# Qwiic_Iridium_9603N.net
KiCad netlist of a schematic drawn in EAGLE
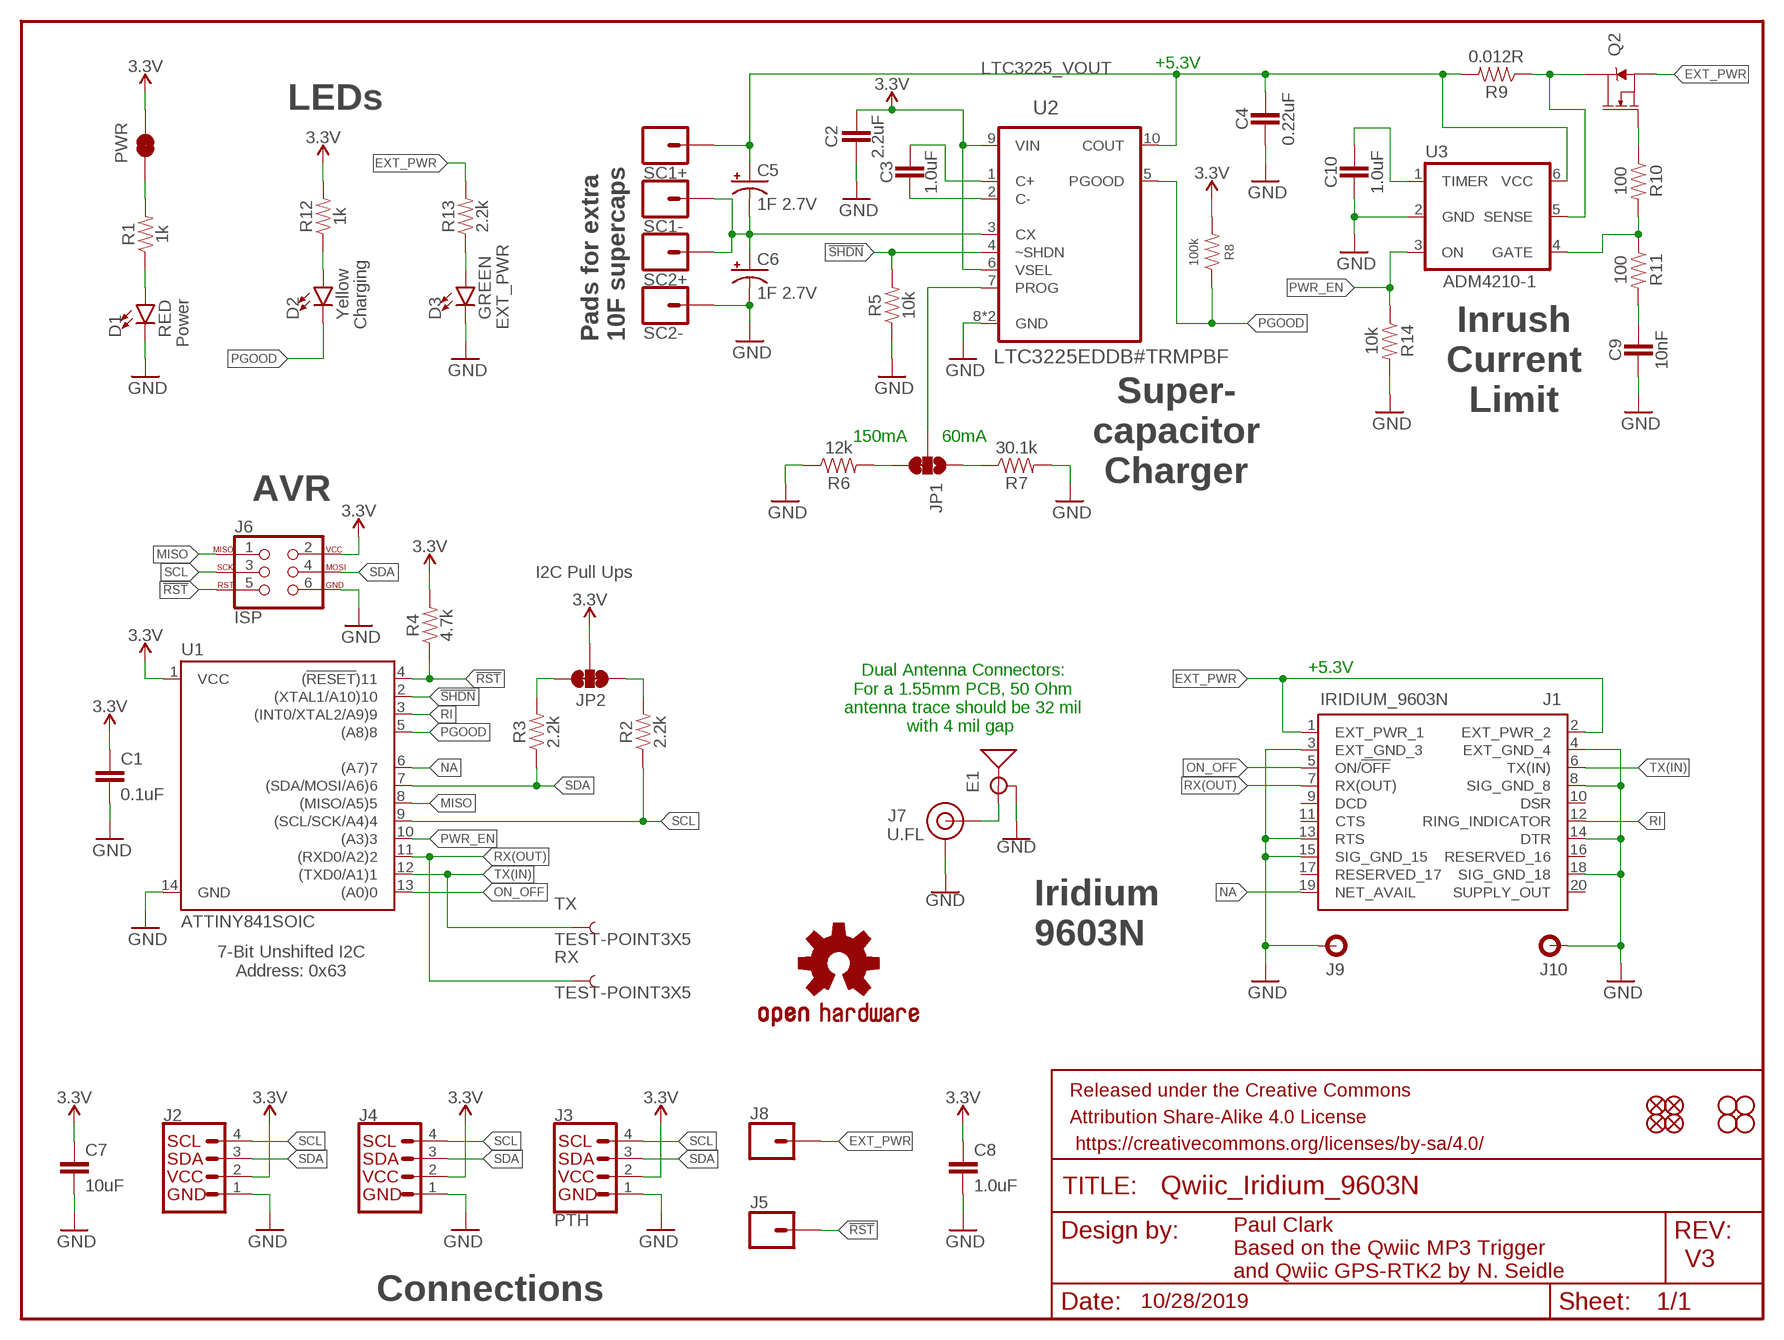
[diagram p0: schematic, sheet 1]

(export (version "E")
  (design (tool "Eeschema 10.0.6"))
  (components
    (comp (ref "C1")
      (value "0.1uF")
      (footprint "eagle-import:0603")
      (libsource (lib "eagle-import") (part "0.1UF-0603-25V-5%"))
    )
    (comp (ref "C2")
      (value "2.2uF")
      (footprint "eagle-import:0603")
      (libsource (lib "eagle-import") (part "2.2UF-0603-10V-20%"))
    )
    (comp (ref "C3")
      (value "1.0uF")
      (footprint "eagle-import:0603")
      (libsource (lib "eagle-import") (part "1.0UF-0603-16V-10%-X7R"))
    )
    (comp (ref "C4")
      (value "0.22uF")
      (footprint "eagle-import:0603")
      (libsource (lib "eagle-import") (part "0.22UF-0603-25V-10%"))
    )
    (comp (ref "C5")
      (value "1F 2.7V")
      (footprint "eagle-import:CPOL-RADIAL-1F-2.7V")
      (libsource (lib "eagle-import") (part "1F-2.7V(PTH)CPOL-RADIAL-1H-2.7V"))
    )
    (comp (ref "C6")
      (value "1F 2.7V")
      (footprint "eagle-import:CPOL-RADIAL-1F-2.7V")
      (libsource (lib "eagle-import") (part "1F-2.7V(PTH)CPOL-RADIAL-1H-2.7V"))
    )
    (comp (ref "C7")
      (value "10uF")
      (footprint "eagle-import:0603")
      (libsource (lib "eagle-import") (part "10UF-0603-6.3V-20%"))
    )
    (comp (ref "C8")
      (value "1.0uF")
      (footprint "eagle-import:0603")
      (libsource (lib "eagle-import") (part "1.0UF-0603-16V-10%-X7R"))
    )
    (comp (ref "C9")
      (value "10nF")
      (footprint "eagle-import:0603")
      (libsource (lib "eagle-import") (part "10NF-0603-50V-10%"))
    )
    (comp (ref "C10")
      (value "1.0uF")
      (footprint "eagle-import:0603")
      (libsource (lib "eagle-import") (part "1.0UF-0603-16V-10%-X7R"))
    )
    (comp (ref "D1")
      (value "RED")
      (footprint "eagle-import:LED-0603")
      (libsource (lib "eagle-import") (part "LED-RED0603"))
    )
    (comp (ref "D2")
      (value "Yellow")
      (footprint "eagle-import:LED-0603")
      (libsource (lib "eagle-import") (part "LED-YELLOW0603"))
    )
    (comp (ref "D3")
      (value "GREEN")
      (footprint "eagle-import:LED-0603")
      (libsource (lib "eagle-import") (part "LED-GREEN0603"))
    )
    (comp (ref "E1")
      (value "ANTENNA-GROUNDEDEDGE_SMA")
      (footprint "eagle-import:SMA-EDGE")
      (libsource (lib "eagle-import") (part "ANTENNA-GROUNDEDEDGE_SMA"))
    )
    (comp (ref "FRAME1")
      (value "FRAME-LETTER")
      (footprint "eagle-import:CREATIVE_COMMONS")
      (libsource (lib "eagle-import") (part "FRAME-LETTER"))
    )
    (comp (ref "J1")
      (value "IRIDIUM_9603N")
      (footprint "eagle-import:IRIDIUM_9603N")
      (libsource (lib "eagle-import") (part "IRIDIUM_9603N"))
    )
    (comp (ref "J2")
      (value "QWIIC_CONNECTORJS-1MM")
      (footprint "eagle-import:JST04_1MM_RA")
      (libsource (lib "eagle-import") (part "QWIIC_CONNECTORJS-1MM"))
    )
    (comp (ref "J3")
      (value "PTH")
      (footprint "eagle-import:1X04_NO_SILK")
      (libsource (lib "eagle-import") (part "I2C_STANDARD_NO_SILK"))
    )
    (comp (ref "J4")
      (value "QWIIC_CONNECTORJS-1MM")
      (footprint "eagle-import:JST04_1MM_RA")
      (libsource (lib "eagle-import") (part "QWIIC_CONNECTORJS-1MM"))
    )
    (comp (ref "J5")
      (value "CONN_01PTH_NO_SILK_YES_STOP")
      (footprint "eagle-import:1X01_NO_SILK")
      (libsource (lib "eagle-import") (part "CONN_01PTH_NO_SILK_YES_STOP"))
    )
    (comp (ref "J6")
      (value "ISP")
      (footprint "eagle-import:2X3_TEST_POINTS")
      (libsource (lib "eagle-import") (part "AVR_SPI_PROG_3X2TESTPOINTS"))
    )
    (comp (ref "J7")
      (value "U.FL")
      (footprint "eagle-import:U.FL")
      (libsource (lib "eagle-import") (part "U.FL2PIN"))
    )
    (comp (ref "J8")
      (value "CONN_01PTH_NO_SILK_YES_STOP")
      (footprint "eagle-import:1X01_NO_SILK")
      (libsource (lib "eagle-import") (part "CONN_01PTH_NO_SILK_YES_STOP"))
    )
    (comp (ref "J9")
      (value "STANDOFFS_M2X0.4_STEEL_6MM")
      (footprint "eagle-import:STANDOFF_M2X0.4")
      (libsource (lib "eagle-import") (part "STANDOFFS_M2X0.4_STEEL_6MM"))
    )
    (comp (ref "J10")
      (value "STANDOFFS_M2X0.4_STEEL_6MM")
      (footprint "eagle-import:STANDOFF_M2X0.4")
      (libsource (lib "eagle-import") (part "STANDOFFS_M2X0.4_STEEL_6MM"))
    )
    (comp (ref "JP1")
      (value "JUMPER-SMT_3_1-NC_TRACE_SILK")
      (footprint "eagle-import:SMT-JUMPER_3_1-NC_TRACE_SILK")
      (libsource (lib "eagle-import") (part "JUMPER-SMT_3_1-NC_TRACE_SILK"))
    )
    (comp (ref "JP2")
      (value "JUMPER-SMT_3_2-NC_TRACE_SILK")
      (footprint "eagle-import:SMT-JUMPER_3_2-NC_TRACE_SILK")
      (libsource (lib "eagle-import") (part "JUMPER-SMT_3_2-NC_TRACE_SILK"))
    )
    (comp (ref "JP3")
      (value "STAND-OFF")
      (footprint "eagle-import:STAND-OFF")
      (libsource (lib "eagle-import") (part "STAND-OFF"))
    )
    (comp (ref "JP4")
      (value "STAND-OFF")
      (footprint "eagle-import:STAND-OFF")
      (libsource (lib "eagle-import") (part "STAND-OFF"))
    )
    (comp (ref "JP5")
      (value "FIDUCIAL1X2")
      (footprint "eagle-import:FIDUCIAL-1X2")
      (libsource (lib "eagle-import") (part "FIDUCIAL1X2"))
    )
    (comp (ref "JP6")
      (value "FIDUCIAL1X2")
      (footprint "eagle-import:FIDUCIAL-1X2")
      (libsource (lib "eagle-import") (part "FIDUCIAL1X2"))
    )
    (comp (ref "JP7")
      (value "FIDUCIAL1X2")
      (footprint "eagle-import:FIDUCIAL-1X2")
      (libsource (lib "eagle-import") (part "FIDUCIAL1X2"))
    )
    (comp (ref "JP8")
      (value "FIDUCIAL1X2")
      (footprint "eagle-import:FIDUCIAL-1X2")
      (libsource (lib "eagle-import") (part "FIDUCIAL1X2"))
    )
    (comp (ref "JP9")
      (value "STAND-OFF")
      (footprint "eagle-import:STAND-OFF")
      (libsource (lib "eagle-import") (part "STAND-OFF"))
    )
    (comp (ref "JP10")
      (value "STAND-OFF")
      (footprint "eagle-import:STAND-OFF")
      (libsource (lib "eagle-import") (part "STAND-OFF"))
    )
    (comp (ref "LOGO1")
      (value "OSHW-LOGOMINI")
      (footprint "eagle-import:OSHW-LOGO-MINI")
      (libsource (lib "eagle-import") (part "OSHW-LOGOMINI"))
    )
    (comp (ref "PWR")
      (value "JUMPER-SMT_2_NC_TRACE_SILK")
      (footprint "eagle-import:SMT-JUMPER_2_NC_TRACE_SILK")
      (libsource (lib "eagle-import") (part "JUMPER-SMT_2_NC_TRACE_SILK"))
    )
    (comp (ref "Q2")
      (value "5.8A/30V/35mΩ")
      (footprint "eagle-import:SOT23-3")
      (libsource (lib "eagle-import") (part "MOSFET-NCH-AO3404A"))
    )
    (comp (ref "R1")
      (value "1k")
      (footprint "eagle-import:0603")
      (libsource (lib "eagle-import") (part "1KOHM-0603-1/10W-1%"))
    )
    (comp (ref "R2")
      (value "2.2k")
      (footprint "eagle-import:0603")
      (libsource (lib "eagle-import") (part "2.2KOHM-0603-1/10W-1%"))
    )
    (comp (ref "R3")
      (value "2.2k")
      (footprint "eagle-import:0603")
      (libsource (lib "eagle-import") (part "2.2KOHM-0603-1/10W-1%"))
    )
    (comp (ref "R4")
      (value "4.7k")
      (footprint "eagle-import:0603")
      (libsource (lib "eagle-import") (part "4.7KOHM-0603-1/10W-1%"))
    )
    (comp (ref "R5")
      (value "10k")
      (footprint "eagle-import:0603")
      (libsource (lib "eagle-import") (part "10KOHM-0603-1/10W-1%"))
    )
    (comp (ref "R6")
      (value "12k")
      (footprint "eagle-import:0603")
      (libsource (lib "eagle-import") (part "12KOHM-0603-1/10W-1%"))
    )
    (comp (ref "R7")
      (value "30.1k")
      (footprint "eagle-import:0603")
      (libsource (lib "eagle-import") (part "30.1KOHM-0603-1/10W-1%"))
    )
    (comp (ref "R8")
      (value "100k")
      (footprint "eagle-import:0603")
      (libsource (lib "eagle-import") (part "100KOHM-0603-1/10W-1%"))
    )
    (comp (ref "R9")
      (value "0.012R")
      (footprint "eagle-import:0603")
      (libsource (lib "eagle-import") (part "RESISTOR_0603_12MILLIOHM0603"))
    )
    (comp (ref "R10")
      (value "100")
      (footprint "eagle-import:0603")
      (libsource (lib "eagle-import") (part "100OHM-0603-1/10W-1%"))
    )
    (comp (ref "R11")
      (value "100")
      (footprint "eagle-import:0603")
      (libsource (lib "eagle-import") (part "100OHM-0603-1/10W-1%"))
    )
    (comp (ref "R12")
      (value "1k")
      (footprint "eagle-import:0603")
      (libsource (lib "eagle-import") (part "1KOHM-0603-1/10W-1%"))
    )
    (comp (ref "R13")
      (value "2.2k")
      (footprint "eagle-import:0603")
      (libsource (lib "eagle-import") (part "2.2KOHM-0603-1/10W-1%"))
    )
    (comp (ref "R14")
      (value "10k")
      (footprint "eagle-import:0603")
      (libsource (lib "eagle-import") (part "10KOHM-0603-1/10W-1%"))
    )
    (comp (ref "RX")
      (value "TEST-POINT3X5")
      (footprint "eagle-import:PAD.03X.05")
      (libsource (lib "eagle-import") (part "TEST-POINT3X5"))
    )
    (comp (ref "SC1+")
      (value "CONN_01PTH_NO_SILK_YES_STOP")
      (footprint "eagle-import:1X01_NO_SILK")
      (libsource (lib "eagle-import") (part "CONN_01PTH_NO_SILK_YES_STOP"))
    )
    (comp (ref "SC1-")
      (value "CONN_01PTH_NO_SILK_YES_STOP")
      (footprint "eagle-import:1X01_NO_SILK")
      (libsource (lib "eagle-import") (part "CONN_01PTH_NO_SILK_YES_STOP"))
    )
    (comp (ref "SC2+")
      (value "CONN_01PTH_NO_SILK_YES_STOP")
      (footprint "eagle-import:1X01_NO_SILK")
      (libsource (lib "eagle-import") (part "CONN_01PTH_NO_SILK_YES_STOP"))
    )
    (comp (ref "SC2-")
      (value "CONN_01PTH_NO_SILK_YES_STOP")
      (footprint "eagle-import:1X01_NO_SILK")
      (libsource (lib "eagle-import") (part "CONN_01PTH_NO_SILK_YES_STOP"))
    )
    (comp (ref "TX")
      (value "TEST-POINT3X5")
      (footprint "eagle-import:PAD.03X.05")
      (libsource (lib "eagle-import") (part "TEST-POINT3X5"))
    )
    (comp (ref "U1")
      (value "ATTINY841SOIC")
      (footprint "eagle-import:ATTINY841")
      (libsource (lib "eagle-import") (part "ATTINY841SOIC"))
    )
    (comp (ref "U2")
      (value "LTC3225EDDB#TRMPBF")
      (footprint "eagle-import:DFN300X200-10L")
      (libsource (lib "eagle-import") (part "LTC3225EDDB-TRMPBFDFN300X200-10L"))
    )
    (comp (ref "U3")
      (value "ADM4210-1")
      (footprint "eagle-import:TSOT6")
      (libsource (lib "eagle-import") (part "ADM4210-1"))
    )
  )
  (nets
    (net (code "1") (name "/LTC3225_VOUT") (class "Default")
      (node (ref "C4") (pin "1") (pinfunction "1_1") (pintype "passive"))
      (node (ref "C5") (pin "+") (pinfunction "+_+") (pintype "passive"))
      (node (ref "R9") (pin "2") (pinfunction "2_2") (pintype "passive"))
      (node (ref "SC1+") (pin "1") (pinfunction "1_1") (pintype "passive"))
      (node (ref "U2") (pin "10") (pinfunction "COUT_10") (pintype "output"))
      (node (ref "U3") (pin "6") (pinfunction "VCC_6") (pintype "power_in"))
    )
    (net (code "2") (name "/~{RST}") (class "Default")
      (node (ref "J5") (pin "1") (pinfunction "1_1") (pintype "passive"))
      (node (ref "J6") (pin "5") (pinfunction "5_5") (pintype "passive"))
      (node (ref "R4") (pin "1") (pinfunction "1_1") (pintype "passive"))
      (node (ref "U1") (pin "4") (pinfunction "(~{RESET})11_4") (pintype "bidirectional"))
    )
    (net (code "3") (name "/~{SHDN}") (class "Default")
      (node (ref "R5") (pin "2") (pinfunction "2_2") (pintype "passive"))
      (node (ref "U1") (pin "2") (pinfunction "(XTAL1/A10)10_2") (pintype "bidirectional"))
      (node (ref "U2") (pin "4") (pinfunction "~{SHDN}_4") (pintype "input"))
    )
    (net (code "4") (name "3.3V") (class "Default")
      (node (ref "C1") (pin "1") (pinfunction "1_1") (pintype "passive"))
      (node (ref "C2") (pin "1") (pinfunction "1_1") (pintype "passive"))
      (node (ref "C7") (pin "1") (pinfunction "1_1") (pintype "passive"))
      (node (ref "C8") (pin "1") (pinfunction "1_1") (pintype "passive"))
      (node (ref "J2") (pin "2") (pinfunction "2_2") (pintype "power_in"))
      (node (ref "J3") (pin "2") (pinfunction "VCC_2") (pintype "power_in"))
      (node (ref "J4") (pin "2") (pinfunction "2_2") (pintype "power_in"))
      (node (ref "J6") (pin "2") (pinfunction "2_2") (pintype "passive"))
      (node (ref "JP2") (pin "2") (pinfunction "2_2") (pintype "passive"))
      (node (ref "PWR") (pin "2") (pinfunction "2_2") (pintype "passive"))
      (node (ref "R12") (pin "2") (pinfunction "2_2") (pintype "passive"))
      (node (ref "R4") (pin "2") (pinfunction "2_2") (pintype "passive"))
      (node (ref "R8") (pin "2") (pinfunction "2_2") (pintype "passive"))
      (node (ref "U1") (pin "1") (pinfunction "VCC_1") (pintype "bidirectional"))
      (node (ref "U2") (pin "6") (pinfunction "VSEL_6") (pintype "input"))
      (node (ref "U2") (pin "9") (pinfunction "VIN_9") (pintype "power_in"))
    )
    (net (code "5") (name "EXT_PWR") (class "Default")
      (node (ref "J1") (pin "1") (pinfunction "EXT_PWR_1_1") (pintype "power_in"))
      (node (ref "J1") (pin "2") (pinfunction "EXT_PWR_2_2") (pintype "power_in"))
      (node (ref "J8") (pin "1") (pinfunction "1_1") (pintype "passive"))
      (node (ref "Q2") (pin "2") (pinfunction "S_2") (pintype "bidirectional"))
      (node (ref "R13") (pin "2") (pinfunction "2_2") (pintype "passive"))
    )
    (net (code "6") (name "GND") (class "Default")
      (node (ref "C1") (pin "2") (pinfunction "2_2") (pintype "passive"))
      (node (ref "C10") (pin "2") (pinfunction "2_2") (pintype "passive"))
      (node (ref "C2") (pin "2") (pinfunction "2_2") (pintype "passive"))
      (node (ref "C4") (pin "2") (pinfunction "2_2") (pintype "passive"))
      (node (ref "C6") (pin "-") (pinfunction "-_-") (pintype "passive"))
      (node (ref "C7") (pin "2") (pinfunction "2_2") (pintype "passive"))
      (node (ref "C8") (pin "2") (pinfunction "2_2") (pintype "passive"))
      (node (ref "C9") (pin "2") (pinfunction "2_2") (pintype "passive"))
      (node (ref "D1") (pin "C") (pinfunction "C_C") (pintype "passive"))
      (node (ref "D3") (pin "C") (pinfunction "C_C") (pintype "passive"))
      (node (ref "E1") (pin "GND@0") (pinfunction "GND_GND@0") (pintype "bidirectional"))
      (node (ref "E1") (pin "GND@1") (pinfunction "GND_GND@1") (pintype "bidirectional"))
      (node (ref "E1") (pin "GND@2") (pinfunction "GND_GND@2") (pintype "bidirectional"))
      (node (ref "E1") (pin "GND@3") (pinfunction "GND_GND@3") (pintype "bidirectional"))
      (node (ref "J1") (pin "13") (pinfunction "RTS_13") (pintype "input"))
      (node (ref "J1") (pin "14") (pinfunction "DTR_14") (pintype "input"))
      (node (ref "J1") (pin "15") (pinfunction "SIG_GND_15_15") (pintype "power_in"))
      (node (ref "J1") (pin "18") (pinfunction "SIG_GND_18_18") (pintype "power_in"))
      (node (ref "J1") (pin "3") (pinfunction "EXT_GND_3_3") (pintype "power_in"))
      (node (ref "J1") (pin "4") (pinfunction "EXT_GND_4_4") (pintype "power_in"))
      (node (ref "J1") (pin "8") (pinfunction "SIG_GND_8_8") (pintype "power_in"))
      (node (ref "J10") (pin "1") (pinfunction "1_1") (pintype "bidirectional"))
      (node (ref "J2") (pin "1") (pinfunction "1_1") (pintype "power_in"))
      (node (ref "J3") (pin "1") (pinfunction "GND_1") (pintype "power_in"))
      (node (ref "J4") (pin "1") (pinfunction "1_1") (pintype "power_in"))
      (node (ref "J6") (pin "6") (pinfunction "6_6") (pintype "passive"))
      (node (ref "J7") (pin "1") (pinfunction "GND_1") (pintype "bidirectional"))
      (node (ref "J7") (pin "2") (pinfunction "GND_2") (pintype "bidirectional"))
      (node (ref "J9") (pin "1") (pinfunction "1_1") (pintype "bidirectional"))
      (node (ref "R14") (pin "2") (pinfunction "2_2") (pintype "passive"))
      (node (ref "R5") (pin "1") (pinfunction "1_1") (pintype "passive"))
      (node (ref "R6") (pin "1") (pinfunction "1_1") (pintype "passive"))
      (node (ref "R7") (pin "2") (pinfunction "2_2") (pintype "passive"))
      (node (ref "SC2-") (pin "1") (pinfunction "1_1") (pintype "passive"))
      (node (ref "U1") (pin "14") (pinfunction "GND_14") (pintype "bidirectional"))
      (node (ref "U2") (pin "11") (pinfunction "GND_11") (pintype "passive"))
      (node (ref "U2") (pin "8") (pinfunction "GND_8") (pintype "passive"))
      (node (ref "U3") (pin "2") (pinfunction "GND_2") (pintype "power_in"))
    )
    (net (code "7") (name "MISO") (class "Default")
      (node (ref "J6") (pin "1") (pinfunction "1_1") (pintype "passive"))
      (node (ref "U1") (pin "8") (pinfunction "(MISO/A5)5_8") (pintype "bidirectional"))
    )
    (net (code "8") (name "NA") (class "Default")
      (node (ref "J1") (pin "19") (pinfunction "NET_AVAIL_19") (pintype "output"))
      (node (ref "U1") (pin "6") (pinfunction "(A7)7_6") (pintype "bidirectional"))
    )
    (net (code "9") (name "Net-(C9-Pad1)") (class "Default")
      (node (ref "C9") (pin "1") (pinfunction "1_1") (pintype "passive"))
      (node (ref "R11") (pin "2") (pinfunction "2_2") (pintype "passive"))
    )
    (net (code "10") (name "Net-(D1-PadA)") (class "Default")
      (node (ref "D1") (pin "A") (pinfunction "A_A") (pintype "passive"))
      (node (ref "R1") (pin "1") (pinfunction "1_1") (pintype "passive"))
    )
    (net (code "11") (name "Net-(D2-PadA)") (class "Default")
      (node (ref "D2") (pin "A") (pinfunction "A_A") (pintype "passive"))
      (node (ref "R12") (pin "1") (pinfunction "1_1") (pintype "passive"))
    )
    (net (code "12") (name "Net-(D3-PadA)") (class "Default")
      (node (ref "D3") (pin "A") (pinfunction "A_A") (pintype "passive"))
      (node (ref "R13") (pin "1") (pinfunction "1_1") (pintype "passive"))
    )
    (net (code "13") (name "Net-(E1-SIGNAL)") (class "Default")
      (node (ref "E1") (pin "SIG") (pinfunction "SIGNAL_SIG") (pintype "bidirectional"))
      (node (ref "J7") (pin "FEED") (pinfunction "SIGNAL_FEED") (pintype "bidirectional"))
    )
    (net (code "14") (name "Net-(JP1-Pad1)") (class "Default")
      (node (ref "JP1") (pin "1") (pinfunction "1_1") (pintype "passive"))
      (node (ref "R7") (pin "1") (pinfunction "1_1") (pintype "passive"))
    )
    (net (code "15") (name "Net-(JP1-Pad3)") (class "Default")
      (node (ref "JP1") (pin "3") (pinfunction "3_3") (pintype "passive"))
      (node (ref "R6") (pin "2") (pinfunction "2_2") (pintype "passive"))
    )
    (net (code "16") (name "Net-(JP2-Pad1)") (class "Default")
      (node (ref "JP2") (pin "1") (pinfunction "1_1") (pintype "passive"))
      (node (ref "R2") (pin "2") (pinfunction "2_2") (pintype "passive"))
    )
    (net (code "17") (name "Net-(JP2-Pad3)") (class "Default")
      (node (ref "JP2") (pin "3") (pinfunction "3_3") (pintype "passive"))
      (node (ref "R3") (pin "2") (pinfunction "2_2") (pintype "passive"))
    )
    (net (code "18") (name "Net-(PWR-Pad1)") (class "Default")
      (node (ref "PWR") (pin "1") (pinfunction "1_1") (pintype "passive"))
      (node (ref "R1") (pin "2") (pinfunction "2_2") (pintype "passive"))
    )
    (net (code "19") (name "Net-(Q2-D)") (class "Default")
      (node (ref "Q2") (pin "3") (pinfunction "D_3") (pintype "bidirectional"))
      (node (ref "R9") (pin "1") (pinfunction "1_1") (pintype "passive"))
      (node (ref "U3") (pin "5") (pinfunction "SENSE_5") (pintype "input"))
    )
    (net (code "20") (name "Net-(Q2-G)") (class "Default")
      (node (ref "Q2") (pin "1") (pinfunction "G_1") (pintype "bidirectional"))
      (node (ref "R10") (pin "1") (pinfunction "1_1") (pintype "passive"))
    )
    (net (code "21") (name "Net-(U2-C+)") (class "Default")
      (node (ref "C3") (pin "1") (pinfunction "1_1") (pintype "passive"))
      (node (ref "U2") (pin "1") (pinfunction "C+_1") (pintype "passive"))
    )
    (net (code "22") (name "Net-(U2-C-)") (class "Default")
      (node (ref "C3") (pin "2") (pinfunction "2_2") (pintype "passive"))
      (node (ref "U2") (pin "2") (pinfunction "C-_2") (pintype "passive"))
    )
    (net (code "23") (name "Net-(U2-CX)") (class "Default")
      (node (ref "C5") (pin "-") (pinfunction "-_-") (pintype "passive"))
      (node (ref "C6") (pin "+") (pinfunction "+_+") (pintype "passive"))
      (node (ref "SC1-") (pin "1") (pinfunction "1_1") (pintype "passive"))
      (node (ref "SC2+") (pin "1") (pinfunction "1_1") (pintype "passive"))
      (node (ref "U2") (pin "3") (pinfunction "CX_3") (pintype "passive"))
    )
    (net (code "24") (name "Net-(U2-PROG)") (class "Default")
      (node (ref "JP1") (pin "2") (pinfunction "2_2") (pintype "passive"))
      (node (ref "U2") (pin "7") (pinfunction "PROG_7") (pintype "input"))
    )
    (net (code "25") (name "Net-(U3-GATE)") (class "Default")
      (node (ref "R10") (pin "2") (pinfunction "2_2") (pintype "passive"))
      (node (ref "R11") (pin "1") (pinfunction "1_1") (pintype "passive"))
      (node (ref "U3") (pin "4") (pinfunction "GATE_4") (pintype "output"))
    )
    (net (code "26") (name "Net-(U3-TIMER)") (class "Default")
      (node (ref "C10") (pin "1") (pinfunction "1_1") (pintype "passive"))
      (node (ref "U3") (pin "1") (pinfunction "TIMER_1") (pintype "input"))
    )
    (net (code "27") (name "ON_OFF") (class "Default")
      (node (ref "J1") (pin "5") (pinfunction "ON/~{OFF}_5") (pintype "input"))
      (node (ref "U1") (pin "13") (pinfunction "(A0)0_13") (pintype "bidirectional"))
    )
    (net (code "28") (name "PGOOD") (class "Default")
      (node (ref "D2") (pin "C") (pinfunction "C_C") (pintype "passive"))
      (node (ref "R8") (pin "1") (pinfunction "1_1") (pintype "passive"))
      (node (ref "U1") (pin "5") (pinfunction "(A8)8_5") (pintype "bidirectional"))
      (node (ref "U2") (pin "5") (pinfunction "PGOOD_5") (pintype "output"))
    )
    (net (code "29") (name "PWR_EN") (class "Default")
      (node (ref "R14") (pin "1") (pinfunction "1_1") (pintype "passive"))
      (node (ref "U1") (pin "10") (pinfunction "(A3)3_10") (pintype "bidirectional"))
      (node (ref "U3") (pin "3") (pinfunction "ON_3") (pintype "input"))
    )
    (net (code "30") (name "RI") (class "Default")
      (node (ref "J1") (pin "12") (pinfunction "RING_INDICATOR_12") (pintype "output"))
      (node (ref "U1") (pin "3") (pinfunction "(INT0/XTAL2/A9)9_3") (pintype "bidirectional"))
    )
    (net (code "31") (name "RX(OUT)") (class "Default")
      (node (ref "J1") (pin "7") (pinfunction "RX(OUT)_7") (pintype "output"))
      (node (ref "RX") (pin "P$1") (pinfunction "1_P$1") (pintype "bidirectional"))
      (node (ref "U1") (pin "11") (pinfunction "(RXD0/A2)2_11") (pintype "bidirectional"))
    )
    (net (code "32") (name "SCL") (class "Default")
      (node (ref "J2") (pin "4") (pinfunction "4_4") (pintype "passive"))
      (node (ref "J3") (pin "4") (pinfunction "SCL_4") (pintype "passive"))
      (node (ref "J4") (pin "4") (pinfunction "4_4") (pintype "passive"))
      (node (ref "J6") (pin "3") (pinfunction "3_3") (pintype "passive"))
      (node (ref "R2") (pin "1") (pinfunction "1_1") (pintype "passive"))
      (node (ref "U1") (pin "9") (pinfunction "(SCL/SCK/A4)4_9") (pintype "bidirectional"))
    )
    (net (code "33") (name "SDA") (class "Default")
      (node (ref "J2") (pin "3") (pinfunction "3_3") (pintype "passive"))
      (node (ref "J3") (pin "3") (pinfunction "SDA_3") (pintype "passive"))
      (node (ref "J4") (pin "3") (pinfunction "3_3") (pintype "passive"))
      (node (ref "J6") (pin "4") (pinfunction "4_4") (pintype "passive"))
      (node (ref "R3") (pin "1") (pinfunction "1_1") (pintype "passive"))
      (node (ref "U1") (pin "7") (pinfunction "(SDA/MOSI/A6)6_7") (pintype "bidirectional"))
    )
    (net (code "34") (name "TX(IN)") (class "Default")
      (node (ref "J1") (pin "6") (pinfunction "TX(IN)_6") (pintype "input"))
      (node (ref "TX") (pin "P$1") (pinfunction "1_P$1") (pintype "bidirectional"))
      (node (ref "U1") (pin "12") (pinfunction "(TXD0/A1)1_12") (pintype "bidirectional"))
    )
    (net (code "35") (name "unconnected-(J1-CTS-Pad11)") (class "Default")
      (node (ref "J1") (pin "11") (pinfunction "CTS_11") (pintype "output"))
    )
    (net (code "36") (name "unconnected-(J1-DCD-Pad9)") (class "Default")
      (node (ref "J1") (pin "9") (pinfunction "DCD_9") (pintype "output"))
    )
    (net (code "37") (name "unconnected-(J1-DSR-Pad10)") (class "Default")
      (node (ref "J1") (pin "10") (pinfunction "DSR_10") (pintype "output"))
    )
    (net (code "38") (name "unconnected-(J1-RESERVED_16-Pad16)") (class "Default")
      (node (ref "J1") (pin "16") (pinfunction "RESERVED_16_16") (pintype "no_connect"))
    )
    (net (code "39") (name "unconnected-(J1-RESERVED_17-Pad17)") (class "Default")
      (node (ref "J1") (pin "17") (pinfunction "RESERVED_17_17") (pintype "no_connect"))
    )
    (net (code "40") (name "unconnected-(J1-SUPPLY_OUT-Pad20)") (class "Default")
      (node (ref "J1") (pin "20") (pinfunction "SUPPLY_OUT_20") (pintype "output"))
    )
  )
)
